# RS485.net
KiCad netlist of a schematic drawn in Altium Designer
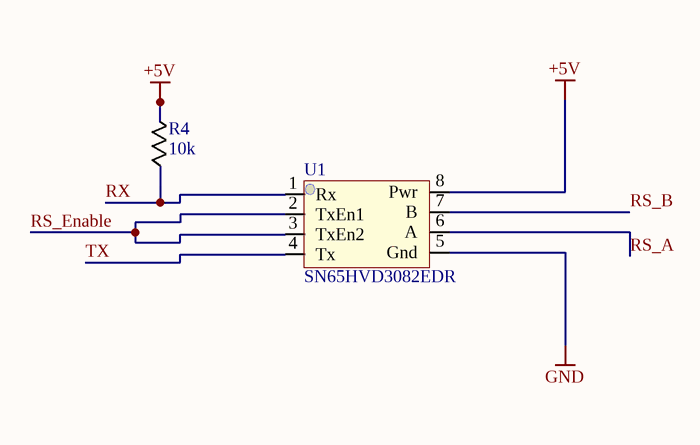
[diagram p0: RS485.SchDoc]

(export (version "E")
  (design (tool "Eeschema 10.0.6"))
  (components
    (comp (ref "R4")
      (value "10k")
      (footprint "0402")
      (description "RC0402FR-0710KL")
      (libsource (lib "kontr") (part "Resistor 0805"))
    )
    (comp (ref "U1") (value "SN65HVD3082EDR") (footprint "SOIC 8") (libsource (lib "kontr") (part "MAX485")))
  )
  (nets
    (net (code "1") (name "+5V") (class "Default")
      (node (ref "R4") (pin "2") (pintype "passive"))
      (node (ref "U1") (pin "8") (pinfunction "Pwr_8") (pintype "passive"))
    )
    (net (code "2") (name "/RS_A") (class "Default")
      (node (ref "U1") (pin "6") (pinfunction "A_6") (pintype "passive"))
    )
    (net (code "3") (name "/RS_B") (class "Default")
      (node (ref "U1") (pin "7") (pinfunction "B_7") (pintype "passive"))
    )
    (net (code "4") (name "/RS_Enable") (class "Default")
      (node (ref "U1") (pin "2") (pinfunction "TxEn1_2") (pintype "passive"))
      (node (ref "U1") (pin "3") (pinfunction "TxEn2_3") (pintype "passive"))
    )
    (net (code "5") (name "/RX") (class "Default")
      (node (ref "R4") (pin "1") (pintype "passive"))
      (node (ref "U1") (pin "1") (pinfunction "Rx_1") (pintype "passive"))
    )
    (net (code "6") (name "/TX") (class "Default")
      (node (ref "U1") (pin "4") (pinfunction "Tx_4") (pintype "passive"))
    )
    (net (code "7") (name "GND") (class "Default")
      (node (ref "U1") (pin "5") (pinfunction "Gnd_5") (pintype "passive"))
    )
  )
)
